# Sheet1.net
KiCad netlist of a schematic drawn in Altium Designer
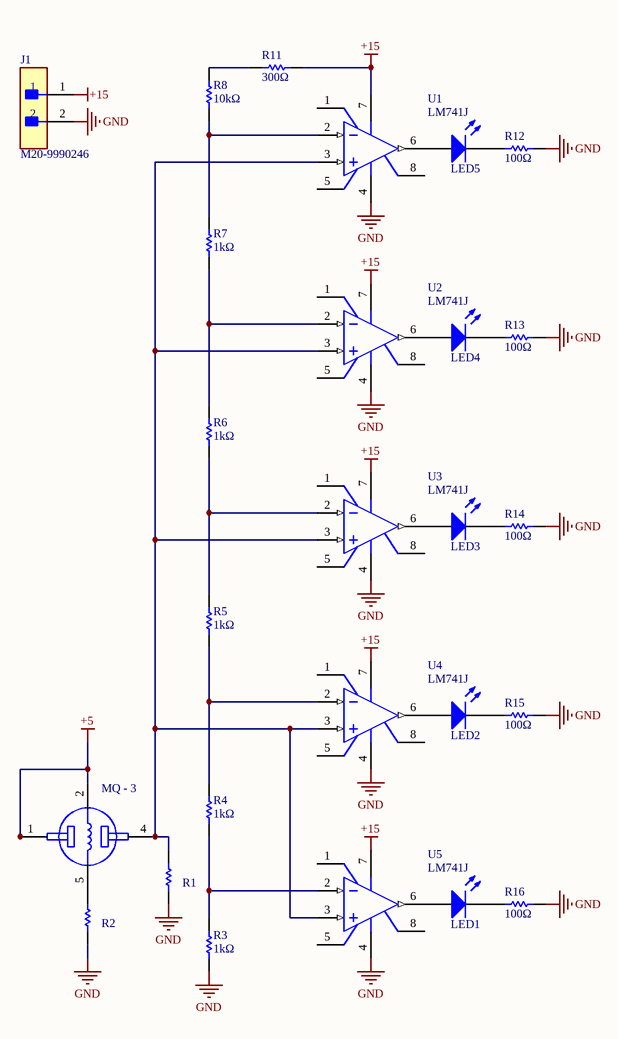
[diagram p0: Sheet1.SchDoc]

(export (version "E")
  (design (tool "Eeschema 10.0.6"))
  (components
    (comp (ref "GROEN")
      (value "LED1")
      (footprint "LED-1")
      (description "Typical RED GaAs LED")
      (fields (field (name "PUBLISHER") "Altium Limited"))
      (libsource (lib "Miscellaneous Devices") (part "LED1"))
    )
    (comp (ref "J1")
      (value "M20-9990246")
      (footprint "FP-M20-9990246-MFG")
      (description "Connector Header Through Hole 2 position 0.100\" (2.54mm)")
      (fields (field (name "OCTOPART") "https://octopart.com/m20-9990246-harwin-2590635"))
      (libsource (lib "Altium Content Vault") (part "3bc925449376181038e59eaffc5286c"))
    )
    (comp (ref "MQ - 3")
      (value "SEN-08880")
      (footprint "XDCR_SEN-08880")
      (description "Alcohol _C2H6O_ Sensor 0 V ~ 3.3 V")
      (fields (field (name "MF") "SparkFun Electronics"))
      (libsource (lib "SEN-08880") (part "SEN-08880"))
    )
    (comp (ref "ORANJE_1")
      (value "LED2")
      (footprint "LED-1")
      (description "Typical RED GaAs LED")
      (fields (field (name "PUBLISHER") "Altium Limited"))
      (libsource (lib "Miscellaneous Devices") (part "LED1"))
    )
    (comp (ref "ORANJE_2")
      (value "LED3")
      (footprint "LED-1")
      (description "Typical RED GaAs LED")
      (fields (field (name "PUBLISHER") "Altium Limited"))
      (libsource (lib "Miscellaneous Devices") (part "LED1"))
    )
    (comp (ref "R1")
      (value "1k Ω")
      (footprint "RESC2013X50X30LL20T20")
      (fields (field (name "MANUFACTURER") "Vishay Dale") (field (name "PART NUMBER") "CRCW08050000Z0EA"))
      (libsource (lib "Altium Content Vault") (part "RES"))
    )
    (comp (ref "R2")
      (value "5,1 Ω")
      (footprint "RESC2013X50X30LL20T20")
      (fields (field (name "MANUFACTURER") "Vishay Dale") (field (name "PART NUMBER") "CRCW08050000Z0EA"))
      (libsource (lib "Altium Content Vault") (part "RES"))
    )
    (comp (ref "R3")
      (value "1kΩ")
      (footprint "RESC2013X50X30LL20T20")
      (fields (field (name "MANUFACTURER") "Vishay Dale") (field (name "PART NUMBER") "CRCW08050000Z0EA"))
      (libsource (lib "Altium Content Vault") (part "RES"))
    )
    (comp (ref "R4")
      (value "1kΩ")
      (footprint "RESC2013X50X30LL20T20")
      (fields (field (name "MANUFACTURER") "Vishay Dale") (field (name "PART NUMBER") "CRCW08050000Z0EA"))
      (libsource (lib "Altium Content Vault") (part "RES"))
    )
    (comp (ref "R5")
      (value "1kΩ")
      (footprint "RESC2013X50X30LL20T20")
      (fields (field (name "MANUFACTURER") "Vishay Dale") (field (name "PART NUMBER") "CRCW08050000Z0EA"))
      (libsource (lib "Altium Content Vault") (part "RES"))
    )
    (comp (ref "R6")
      (value "1kΩ")
      (footprint "RESC2013X50X30LL20T20")
      (fields (field (name "MANUFACTURER") "Vishay Dale") (field (name "PART NUMBER") "CRCW08050000Z0EA"))
      (libsource (lib "Altium Content Vault") (part "RES"))
    )
    (comp (ref "R7")
      (value "1kΩ")
      (footprint "RESC2013X50X30LL20T20")
      (fields (field (name "MANUFACTURER") "Vishay Dale") (field (name "PART NUMBER") "CRCW08050000Z0EA"))
      (libsource (lib "Altium Content Vault") (part "RES"))
    )
    (comp (ref "R8")
      (value "10kΩ")
      (footprint "RESC2013X50X30LL20T20")
      (fields (field (name "MANUFACTURER") "Vishay Dale") (field (name "PART NUMBER") "CRCW08050000Z0EA"))
      (libsource (lib "Altium Content Vault") (part "RES"))
    )
    (comp (ref "R11")
      (value "300Ω")
      (footprint "RESC2013X50X30LL20T20")
      (fields (field (name "MANUFACTURER") "Vishay Dale") (field (name "PART NUMBER") "CRCW08050000Z0EA"))
      (libsource (lib "Altium Content Vault") (part "RES"))
    )
    (comp (ref "R12")
      (value "100Ω")
      (footprint "RESC2013X50X30LL20T20")
      (fields (field (name "MANUFACTURER") "Vishay Dale") (field (name "PART NUMBER") "CRCW08050000Z0EA"))
      (libsource (lib "Altium Content Vault") (part "RES"))
    )
    (comp (ref "R13")
      (value "100Ω")
      (footprint "RESC2013X50X30LL20T20")
      (fields (field (name "MANUFACTURER") "Vishay Dale") (field (name "PART NUMBER") "CRCW08050000Z0EA"))
      (libsource (lib "Altium Content Vault") (part "RES"))
    )
    (comp (ref "R14")
      (value "100Ω")
      (footprint "RESC2013X50X30LL20T20")
      (fields (field (name "MANUFACTURER") "Vishay Dale") (field (name "PART NUMBER") "CRCW08050000Z0EA"))
      (libsource (lib "Altium Content Vault") (part "RES"))
    )
    (comp (ref "R15")
      (value "100Ω")
      (footprint "RESC2013X50X30LL20T20")
      (fields (field (name "MANUFACTURER") "Vishay Dale") (field (name "PART NUMBER") "CRCW08050000Z0EA"))
      (libsource (lib "Altium Content Vault") (part "RES"))
    )
    (comp (ref "R16")
      (value "100Ω")
      (footprint "RESC2013X50X30LL20T20")
      (fields (field (name "MANUFACTURER") "Vishay Dale") (field (name "PART NUMBER") "CRCW08050000Z0EA"))
      (libsource (lib "Altium Content Vault") (part "RES"))
    )
    (comp (ref "ROOD_1")
      (value "LED4")
      (footprint "LED-1")
      (description "Typical RED GaAs LED")
      (fields (field (name "PUBLISHER") "Altium Limited"))
      (libsource (lib "Miscellaneous Devices") (part "LED1"))
    )
    (comp (ref "ROOD_2")
      (value "LED5")
      (footprint "LED-1")
      (description "Typical RED GaAs LED")
      (fields (field (name "PUBLISHER") "Altium Limited"))
      (libsource (lib "Miscellaneous Devices") (part "LED1"))
    )
    (comp (ref "U1")
      (value "LM741J")
      (footprint "NAB0008A")
      (description "Operational Amplifier, 8-pin CerDIP")
      (fields (field (name "MANUFACTURER") "Texas Instruments"))
      (libsource (lib "Altium Content Vault") (part "AMP-OPA-LM741-8"))
    )
    (comp (ref "U2")
      (value "LM741J")
      (footprint "NAB0008A")
      (description "Operational Amplifier, 8-pin CerDIP")
      (fields (field (name "MANUFACTURER") "Texas Instruments"))
      (libsource (lib "Altium Content Vault") (part "AMP-OPA-LM741-8"))
    )
    (comp (ref "U3")
      (value "LM741J")
      (footprint "NAB0008A")
      (description "Operational Amplifier, 8-pin CerDIP")
      (fields (field (name "MANUFACTURER") "Texas Instruments"))
      (libsource (lib "Altium Content Vault") (part "AMP-OPA-LM741-8"))
    )
    (comp (ref "U4")
      (value "LM741J")
      (footprint "NAB0008A")
      (description "Operational Amplifier, 8-pin CerDIP")
      (fields (field (name "MANUFACTURER") "Texas Instruments"))
      (libsource (lib "Altium Content Vault") (part "AMP-OPA-LM741-8"))
    )
    (comp (ref "U5")
      (value "LM741J")
      (footprint "NAB0008A")
      (description "Operational Amplifier, 8-pin CerDIP")
      (fields (field (name "MANUFACTURER") "Texas Instruments"))
      (libsource (lib "Altium Content Vault") (part "AMP-OPA-LM741-8"))
    )
  )
  (nets
    (net (code "1") (name "+5") (class "Default")
      (node (ref "MQ - 3") (pin "1") (pinfunction "A_1") (pintype "passive"))
      (node (ref "MQ - 3") (pin "2") (pinfunction "H1_2") (pintype "passive"))
      (node (ref "MQ - 3") (pin "3") (pinfunction "A_3") (pintype "passive"))
    )
    (net (code "2") (name "+15") (class "Default")
      (node (ref "J1") (pin "1") (pinfunction "1_1") (pintype "passive"))
      (node (ref "R11") (pin "1") (pinfunction "1_1") (pintype "passive"))
      (node (ref "U1") (pin "7") (pinfunction "V+_7") (pintype "power_in"))
      (node (ref "U2") (pin "7") (pinfunction "V+_7") (pintype "power_in"))
      (node (ref "U3") (pin "7") (pinfunction "V+_7") (pintype "power_in"))
      (node (ref "U4") (pin "7") (pinfunction "V+_7") (pintype "power_in"))
      (node (ref "U5") (pin "7") (pinfunction "V+_7") (pintype "power_in"))
    )
    (net (code "3") (name "GND") (class "Default")
      (node (ref "J1") (pin "2") (pinfunction "2_2") (pintype "passive"))
      (node (ref "R1") (pin "1") (pinfunction "1_1") (pintype "passive"))
      (node (ref "R12") (pin "1") (pinfunction "1_1") (pintype "passive"))
      (node (ref "R13") (pin "1") (pinfunction "1_1") (pintype "passive"))
      (node (ref "R14") (pin "1") (pinfunction "1_1") (pintype "passive"))
      (node (ref "R15") (pin "1") (pinfunction "1_1") (pintype "passive"))
      (node (ref "R16") (pin "1") (pinfunction "1_1") (pintype "passive"))
      (node (ref "R2") (pin "1") (pinfunction "1_1") (pintype "passive"))
      (node (ref "R3") (pin "1") (pinfunction "1_1") (pintype "passive"))
      (node (ref "U1") (pin "4") (pinfunction "V-_4") (pintype "power_in"))
      (node (ref "U2") (pin "4") (pinfunction "V-_4") (pintype "power_in"))
      (node (ref "U3") (pin "4") (pinfunction "V-_4") (pintype "power_in"))
      (node (ref "U4") (pin "4") (pinfunction "V-_4") (pintype "power_in"))
      (node (ref "U5") (pin "4") (pinfunction "V-_4") (pintype "power_in"))
    )
    (net (code "4") (name "Net-(GROEN-A)") (class "Default")
      (node (ref "GROEN") (pin "1") (pinfunction "A_1") (pintype "passive"))
      (node (ref "U5") (pin "6") (pinfunction "OUT_6") (pintype "output"))
    )
    (net (code "5") (name "Net-(GROEN-K)") (class "Default")
      (node (ref "GROEN") (pin "2") (pinfunction "K_2") (pintype "passive"))
      (node (ref "R16") (pin "2") (pinfunction "2_2") (pintype "passive"))
    )
    (net (code "6") (name "Net-(MQ - 3-H2)") (class "Default")
      (node (ref "MQ - 3") (pin "5") (pinfunction "H2_5") (pintype "passive"))
      (node (ref "R2") (pin "2") (pinfunction "2_2") (pintype "passive"))
    )
    (net (code "7") (name "Net-(ORANJE_1-A)") (class "Default")
      (node (ref "ORANJE_1") (pin "1") (pinfunction "A_1") (pintype "passive"))
      (node (ref "U4") (pin "6") (pinfunction "OUT_6") (pintype "output"))
    )
    (net (code "8") (name "Net-(ORANJE_1-K)") (class "Default")
      (node (ref "ORANJE_1") (pin "2") (pinfunction "K_2") (pintype "passive"))
      (node (ref "R15") (pin "2") (pinfunction "2_2") (pintype "passive"))
    )
    (net (code "9") (name "Net-(ORANJE_2-A)") (class "Default")
      (node (ref "ORANJE_2") (pin "1") (pinfunction "A_1") (pintype "passive"))
      (node (ref "U3") (pin "6") (pinfunction "OUT_6") (pintype "output"))
    )
    (net (code "10") (name "Net-(ORANJE_2-K)") (class "Default")
      (node (ref "ORANJE_2") (pin "2") (pinfunction "K_2") (pintype "passive"))
      (node (ref "R14") (pin "2") (pinfunction "2_2") (pintype "passive"))
    )
    (net (code "11") (name "Net-(R11-Pad2)") (class "Default")
      (node (ref "R11") (pin "2") (pinfunction "2_2") (pintype "passive"))
      (node (ref "R8") (pin "2") (pinfunction "2_2") (pintype "passive"))
    )
    (net (code "12") (name "Net-(ROOD_1-A)") (class "Default")
      (node (ref "ROOD_1") (pin "1") (pinfunction "A_1") (pintype "passive"))
      (node (ref "U2") (pin "6") (pinfunction "OUT_6") (pintype "output"))
    )
    (net (code "13") (name "Net-(ROOD_1-K)") (class "Default")
      (node (ref "R13") (pin "2") (pinfunction "2_2") (pintype "passive"))
      (node (ref "ROOD_1") (pin "2") (pinfunction "K_2") (pintype "passive"))
    )
    (net (code "14") (name "Net-(ROOD_2-A)") (class "Default")
      (node (ref "ROOD_2") (pin "1") (pinfunction "A_1") (pintype "passive"))
      (node (ref "U1") (pin "6") (pinfunction "OUT_6") (pintype "output"))
    )
    (net (code "15") (name "Net-(ROOD_2-K)") (class "Default")
      (node (ref "R12") (pin "2") (pinfunction "2_2") (pintype "passive"))
      (node (ref "ROOD_2") (pin "2") (pinfunction "K_2") (pintype "passive"))
    )
    (net (code "16") (name "Net-(U1-IN+)") (class "Default")
      (node (ref "MQ - 3") (pin "4") (pinfunction "B_4") (pintype "passive"))
      (node (ref "MQ - 3") (pin "6") (pinfunction "B_6") (pintype "passive"))
      (node (ref "R1") (pin "2") (pinfunction "2_2") (pintype "passive"))
      (node (ref "U1") (pin "3") (pinfunction "IN+_3") (pintype "input"))
      (node (ref "U2") (pin "3") (pinfunction "IN+_3") (pintype "input"))
      (node (ref "U3") (pin "3") (pinfunction "IN+_3") (pintype "input"))
      (node (ref "U4") (pin "3") (pinfunction "IN+_3") (pintype "input"))
      (node (ref "U5") (pin "3") (pinfunction "IN+_3") (pintype "input"))
    )
    (net (code "17") (name "Net-(U1-IN-)") (class "Default")
      (node (ref "R7") (pin "2") (pinfunction "2_2") (pintype "passive"))
      (node (ref "R8") (pin "1") (pinfunction "1_1") (pintype "passive"))
      (node (ref "U1") (pin "2") (pinfunction "IN-_2") (pintype "input"))
    )
    (net (code "18") (name "Net-(U2-IN-)") (class "Default")
      (node (ref "R6") (pin "2") (pinfunction "2_2") (pintype "passive"))
      (node (ref "R7") (pin "1") (pinfunction "1_1") (pintype "passive"))
      (node (ref "U2") (pin "2") (pinfunction "IN-_2") (pintype "input"))
    )
    (net (code "19") (name "Net-(U3-IN-)") (class "Default")
      (node (ref "R5") (pin "2") (pinfunction "2_2") (pintype "passive"))
      (node (ref "R6") (pin "1") (pinfunction "1_1") (pintype "passive"))
      (node (ref "U3") (pin "2") (pinfunction "IN-_2") (pintype "input"))
    )
    (net (code "20") (name "Net-(U4-IN-)") (class "Default")
      (node (ref "R4") (pin "2") (pinfunction "2_2") (pintype "passive"))
      (node (ref "R5") (pin "1") (pinfunction "1_1") (pintype "passive"))
      (node (ref "U4") (pin "2") (pinfunction "IN-_2") (pintype "input"))
    )
    (net (code "21") (name "Net-(U5-IN-)") (class "Default")
      (node (ref "R3") (pin "2") (pinfunction "2_2") (pintype "passive"))
      (node (ref "R4") (pin "1") (pinfunction "1_1") (pintype "passive"))
      (node (ref "U5") (pin "2") (pinfunction "IN-_2") (pintype "input"))
    )
    (net (code "22") (name "unconnected-(U1-NC-Pad8)") (class "Default")
      (node (ref "U1") (pin "8") (pinfunction "NC_8") (pintype "passive"))
    )
    (net (code "23") (name "unconnected-(U1-OFS_NULL-Pad1)") (class "Default")
      (node (ref "U1") (pin "1") (pinfunction "OFS_NULL_1") (pintype "passive"))
    )
    (net (code "24") (name "unconnected-(U1-OFS_NULL-Pad5)") (class "Default")
      (node (ref "U1") (pin "5") (pinfunction "OFS_NULL_5") (pintype "passive"))
    )
    (net (code "25") (name "unconnected-(U2-NC-Pad8)") (class "Default")
      (node (ref "U2") (pin "8") (pinfunction "NC_8") (pintype "passive"))
    )
    (net (code "26") (name "unconnected-(U2-OFS_NULL-Pad1)") (class "Default")
      (node (ref "U2") (pin "1") (pinfunction "OFS_NULL_1") (pintype "passive"))
    )
    (net (code "27") (name "unconnected-(U2-OFS_NULL-Pad5)") (class "Default")
      (node (ref "U2") (pin "5") (pinfunction "OFS_NULL_5") (pintype "passive"))
    )
    (net (code "28") (name "unconnected-(U3-NC-Pad8)") (class "Default")
      (node (ref "U3") (pin "8") (pinfunction "NC_8") (pintype "passive"))
    )
    (net (code "29") (name "unconnected-(U3-OFS_NULL-Pad1)") (class "Default")
      (node (ref "U3") (pin "1") (pinfunction "OFS_NULL_1") (pintype "passive"))
    )
    (net (code "30") (name "unconnected-(U3-OFS_NULL-Pad5)") (class "Default")
      (node (ref "U3") (pin "5") (pinfunction "OFS_NULL_5") (pintype "passive"))
    )
    (net (code "31") (name "unconnected-(U4-NC-Pad8)") (class "Default")
      (node (ref "U4") (pin "8") (pinfunction "NC_8") (pintype "passive"))
    )
    (net (code "32") (name "unconnected-(U4-OFS_NULL-Pad1)") (class "Default")
      (node (ref "U4") (pin "1") (pinfunction "OFS_NULL_1") (pintype "passive"))
    )
    (net (code "33") (name "unconnected-(U4-OFS_NULL-Pad5)") (class "Default")
      (node (ref "U4") (pin "5") (pinfunction "OFS_NULL_5") (pintype "passive"))
    )
    (net (code "34") (name "unconnected-(U5-NC-Pad8)") (class "Default")
      (node (ref "U5") (pin "8") (pinfunction "NC_8") (pintype "passive"))
    )
    (net (code "35") (name "unconnected-(U5-OFS_NULL-Pad1)") (class "Default")
      (node (ref "U5") (pin "1") (pinfunction "OFS_NULL_1") (pintype "passive"))
    )
    (net (code "36") (name "unconnected-(U5-OFS_NULL-Pad5)") (class "Default")
      (node (ref "U5") (pin "5") (pinfunction "OFS_NULL_5") (pintype "passive"))
    )
  )
)
